# DfMUX_ADC.net
KiCad netlist of a schematic drawn in Altium Designer
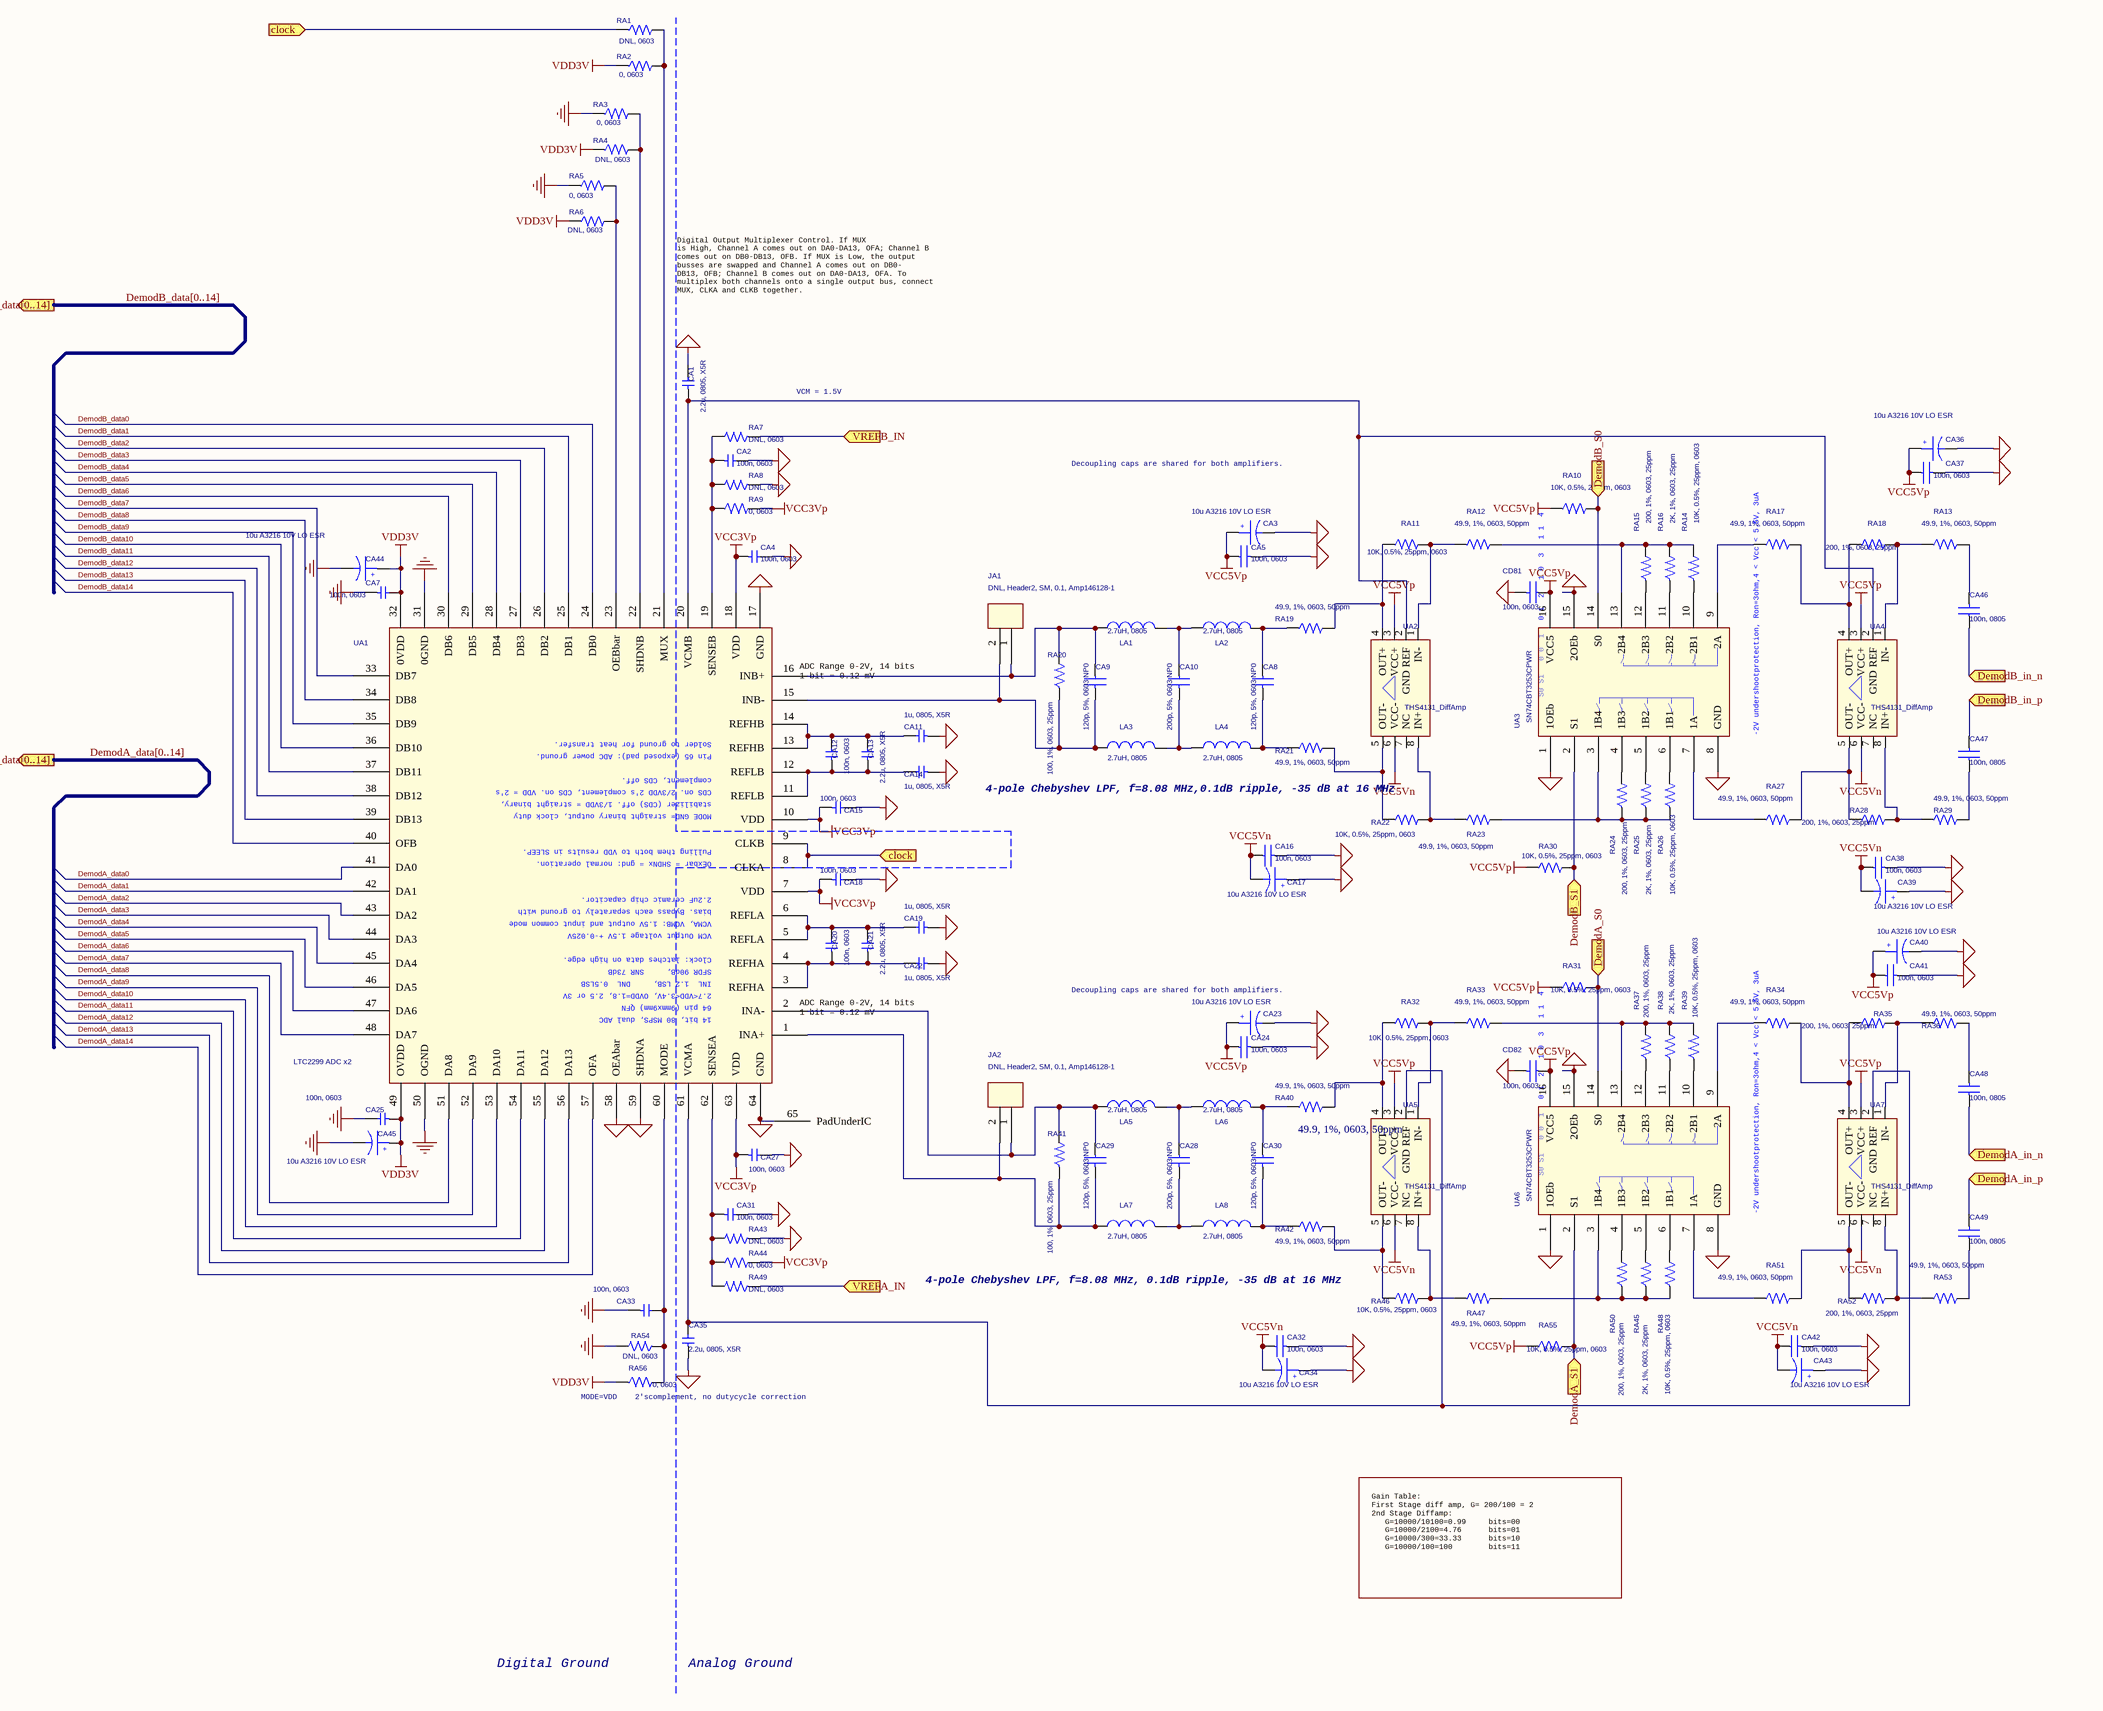
[diagram p0: DfMUX_ADC.SchDoc]

(export (version "E")
  (design (tool "Eeschema 10.0.6"))
  (components
    (comp (ref "CA1") (value "2.2u, 0805, X5R") (footprint "0805C") (libsource (lib "*") (part "C")))
    (comp (ref "CA2") (value "100n, 0603") (footprint "0603C") (libsource (lib "*") (part "C")))
    (comp (ref "CA3") (value "10u A3216 10V LO ESR") (libsource (lib "*") (part "CAPACITOR POL")))
    (comp (ref "CA4") (value "100n, 0603") (footprint "0603C") (libsource (lib "*") (part "C")))
    (comp (ref "CA5")
      (value "100n, 0603")
      (footprint "0603C")
      (libsource (lib "*") (part "CAPACITOR NON-POL"))
    )
    (comp (ref "CA7") (value "100n, 0603") (footprint "0603C") (libsource (lib "*") (part "C")))
    (comp (ref "CA8")
      (value "120p, 5%, 0603 NP0")
      (footprint "0603C")
      (libsource (lib "*") (part "CAPACITOR NON-POL"))
    )
    (comp (ref "CA9")
      (value "120p, 5%, 0603 NP0")
      (footprint "0603C")
      (libsource (lib "*") (part "CAPACITOR NON-POL"))
    )
    (comp (ref "CA10")
      (value "200p, 5%, 0603 NP0")
      (footprint "0603C")
      (libsource (lib "*") (part "CAPACITOR NON-POL"))
    )
    (comp (ref "CA11") (value "1u, 0805, X5R") (footprint "0805C") (libsource (lib "*") (part "C")))
    (comp (ref "CA12") (value "100n, 0603") (footprint "0603C") (libsource (lib "*") (part "C")))
    (comp (ref "CA13") (value "2.2u, 0805, X5R") (footprint "0805C") (libsource (lib "*") (part "C")))
    (comp (ref "CA14") (value "1u, 0805, X5R") (footprint "0805C") (libsource (lib "*") (part "C")))
    (comp (ref "CA15") (value "100n, 0603") (footprint "0603C") (libsource (lib "*") (part "C")))
    (comp (ref "CA16")
      (value "100n, 0603")
      (footprint "0603C")
      (libsource (lib "*") (part "CAPACITOR NON-POL"))
    )
    (comp (ref "CA17") (value "10u A3216 10V LO ESR") (libsource (lib "*") (part "CAPACITOR POL")))
    (comp (ref "CA18") (value "100n, 0603") (footprint "0603C") (libsource (lib "*") (part "C")))
    (comp (ref "CA19") (value "1u, 0805, X5R") (footprint "0805C") (libsource (lib "*") (part "C")))
    (comp (ref "CA20") (value "100n, 0603") (footprint "0603C") (libsource (lib "*") (part "C")))
    (comp (ref "CA21") (value "2.2u, 0805, X5R") (footprint "0805C") (libsource (lib "*") (part "C")))
    (comp (ref "CA22") (value "1u, 0805, X5R") (footprint "0805C") (libsource (lib "*") (part "C")))
    (comp (ref "CA23") (value "10u A3216 10V LO ESR") (libsource (lib "*") (part "CAPACITOR POL")))
    (comp (ref "CA24")
      (value "100n, 0603")
      (footprint "0603C")
      (libsource (lib "*") (part "CAPACITOR NON-POL"))
    )
    (comp (ref "CA25") (value "100n, 0603") (footprint "0603C") (libsource (lib "*") (part "C")))
    (comp (ref "CA27") (value "100n, 0603") (footprint "0603C") (libsource (lib "*") (part "C")))
    (comp (ref "CA28") (value "200p, 5%, 0603 NP0") (libsource (lib "*") (part "CAPACITOR NON-POL")))
    (comp (ref "CA29")
      (value "120p, 5%, 0603 NP0")
      (footprint "0603C")
      (libsource (lib "*") (part "CAPACITOR NON-POL"))
    )
    (comp (ref "CA30")
      (value "120p, 5%, 0603 NP0")
      (footprint "0603C")
      (libsource (lib "*") (part "CAPACITOR NON-POL"))
    )
    (comp (ref "CA31") (value "100n, 0603") (footprint "0603C") (libsource (lib "*") (part "C")))
    (comp (ref "CA32")
      (value "100n, 0603")
      (footprint "0603C")
      (libsource (lib "*") (part "CAPACITOR NON-POL"))
    )
    (comp (ref "CA33") (value "100n, 0603") (footprint "0603C") (libsource (lib "*") (part "C")))
    (comp (ref "CA34") (value "10u A3216 10V LO ESR") (libsource (lib "*") (part "CAPACITOR POL")))
    (comp (ref "CA35") (value "2.2u, 0805, X5R") (footprint "0805C") (libsource (lib "*") (part "C")))
    (comp (ref "CA36") (value "10u A3216 10V LO ESR") (libsource (lib "*") (part "CAPACITOR POL")))
    (comp (ref "CA37")
      (value "100n, 0603")
      (footprint "0603C")
      (libsource (lib "*") (part "CAPACITOR NON-POL"))
    )
    (comp (ref "CA38")
      (value "100n, 0603")
      (footprint "0603C")
      (libsource (lib "*") (part "CAPACITOR NON-POL"))
    )
    (comp (ref "CA39") (value "10u A3216 10V LO ESR") (libsource (lib "*") (part "CAPACITOR POL")))
    (comp (ref "CA40") (value "10u A3216 10V LO ESR") (libsource (lib "*") (part "CAPACITOR POL")))
    (comp (ref "CA41")
      (value "100n, 0603")
      (footprint "0603C")
      (libsource (lib "*") (part "CAPACITOR NON-POL"))
    )
    (comp (ref "CA42")
      (value "100n, 0603")
      (footprint "0603C")
      (libsource (lib "*") (part "CAPACITOR NON-POL"))
    )
    (comp (ref "CA43") (value "10u A3216 10V LO ESR") (libsource (lib "*") (part "CAPACITOR POL")))
    (comp (ref "CA44") (value "10u A3216 10V LO ESR") (libsource (lib "*") (part "CAPACITOR POL")))
    (comp (ref "CA45") (value "10u A3216 10V LO ESR") (libsource (lib "*") (part "CAPACITOR POL")))
    (comp (ref "CA46")
      (value "100n, 0805")
      (footprint "0805C")
      (libsource (lib "*") (part "CAPACITOR NON-POL"))
    )
    (comp (ref "CA47")
      (value "100n, 0805")
      (footprint "0805C")
      (libsource (lib "*") (part "CAPACITOR NON-POL"))
    )
    (comp (ref "CA48")
      (value "100n, 0805")
      (footprint "0805C")
      (libsource (lib "*") (part "CAPACITOR NON-POL"))
    )
    (comp (ref "CA49")
      (value "100n, 0805")
      (footprint "0805C")
      (libsource (lib "*") (part "CAPACITOR NON-POL"))
    )
    (comp (ref "CD81")
      (value "100n, 0603")
      (footprint "0603C")
      (libsource (lib "*") (part "CAPACITOR NON-POL"))
    )
    (comp (ref "CD82")
      (value "100n, 0603")
      (footprint "0603C")
      (libsource (lib "*") (part "CAPACITOR NON-POL"))
    )
    (comp (ref "JA1")
      (value "DNL, Header2, SM, 0.1, Amp146128-1")
      (libsource (lib "*") (part "CONN_TRBLK_2"))
    )
    (comp (ref "JA2")
      (value "DNL, Header2, SM, 0.1, Amp146128-1")
      (libsource (lib "*") (part "CONN_TRBLK_2"))
    )
    (comp (ref "LA1") (value "2.7uH, 0805") (libsource (lib "*") (part "INDUCTOR/SM")))
    (comp (ref "LA2") (value "2.7uH, 0805") (libsource (lib "*") (part "INDUCTOR/SM")))
    (comp (ref "LA3") (value "2.7uH, 0805") (libsource (lib "*") (part "INDUCTOR/SM")))
    (comp (ref "LA4") (value "2.7uH, 0805") (libsource (lib "*") (part "INDUCTOR/SM")))
    (comp (ref "LA5") (value "2.7uH, 0805") (libsource (lib "*") (part "INDUCTOR/SM")))
    (comp (ref "LA6") (value "2.7uH, 0805") (libsource (lib "*") (part "INDUCTOR/SM")))
    (comp (ref "LA7") (value "2.7uH, 0805") (libsource (lib "*") (part "INDUCTOR/SM")))
    (comp (ref "LA8") (value "2.7uH, 0805") (libsource (lib "*") (part "INDUCTOR/SM")))
    (comp (ref "RA1") (value "DNL, 0603") (footprint "0603R") (libsource (lib "*") (part "R_Dup2")))
    (comp (ref "RA2") (value "0, 0603") (footprint "0603R") (libsource (lib "*") (part "R_Dup2")))
    (comp (ref "RA3") (value "0, 0603") (footprint "0603R") (libsource (lib "*") (part "R_Dup2")))
    (comp (ref "RA4") (value "DNL, 0603") (footprint "0603R") (libsource (lib "*") (part "R_Dup2")))
    (comp (ref "RA5") (value "0, 0603") (footprint "0603R") (libsource (lib "*") (part "R_Dup2")))
    (comp (ref "RA6") (value "DNL, 0603") (footprint "0603R") (libsource (lib "*") (part "R_Dup2")))
    (comp (ref "RA7") (value "DNL, 0603") (footprint "0603R") (libsource (lib "*") (part "R_Dup2")))
    (comp (ref "RA8") (value "DNL, 0603") (footprint "0603R") (libsource (lib "*") (part "R_Dup2")))
    (comp (ref "RA9") (value "0, 0603") (footprint "0603R") (libsource (lib "*") (part "R_Dup2")))
    (comp (ref "RA10")
      (value "10K, 0.5%, 25ppm, 0603")
      (footprint "0603R")
      (libsource (lib "*") (part "R_Dup2"))
    )
    (comp (ref "RA11")
      (value "10K, 0.5%, 25ppm, 0603")
      (footprint "0603R")
      (libsource (lib "*") (part "R_Dup2"))
    )
    (comp (ref "RA12")
      (value "49.9, 1%, 0603, 50ppm")
      (footprint "0603R")
      (libsource (lib "*") (part "R_Dup2"))
    )
    (comp (ref "RA13")
      (value "49.9, 1%, 0603, 50ppm")
      (footprint "0603R")
      (libsource (lib "*") (part "R_Dup2"))
    )
    (comp (ref "RA14")
      (value "10K, 0.5%, 25ppm, 0603")
      (footprint "0603R")
      (libsource (lib "*") (part "R_Dup2"))
    )
    (comp (ref "RA15")
      (value "200, 1%, 0603, 25ppm")
      (footprint "0603R")
      (libsource (lib "*") (part "R_Dup2"))
    )
    (comp (ref "RA16")
      (value "2K, 1%, 0603, 25ppm")
      (footprint "0603R")
      (libsource (lib "*") (part "R_Dup2"))
    )
    (comp (ref "RA17")
      (value "49.9, 1%, 0603, 50ppm")
      (footprint "0603R")
      (libsource (lib "*") (part "R_Dup2"))
    )
    (comp (ref "RA18")
      (value "200, 1%, 0603, 25ppm")
      (footprint "0603R")
      (libsource (lib "*") (part "R_Dup2"))
    )
    (comp (ref "RA19")
      (value "49.9, 1%, 0603, 50ppm")
      (footprint "0603R")
      (libsource (lib "*") (part "R_Dup2"))
    )
    (comp (ref "RA20")
      (value "100, 1%, 0603, 25ppm")
      (footprint "0603R")
      (libsource (lib "*") (part "R_Dup2"))
    )
    (comp (ref "RA21")
      (value "49.9, 1%, 0603, 50ppm")
      (footprint "0603R")
      (libsource (lib "*") (part "R_Dup2"))
    )
    (comp (ref "RA22")
      (value "10K, 0.5%, 25ppm, 0603")
      (footprint "0603R")
      (libsource (lib "*") (part "R_Dup2"))
    )
    (comp (ref "RA23")
      (value "49.9, 1%, 0603, 50ppm")
      (footprint "0603R")
      (libsource (lib "*") (part "R_Dup2"))
    )
    (comp (ref "RA24")
      (value "200, 1%, 0603, 25ppm")
      (footprint "0603R")
      (libsource (lib "*") (part "R_Dup2"))
    )
    (comp (ref "RA25")
      (value "2K, 1%, 0603, 25ppm")
      (footprint "0603R")
      (libsource (lib "*") (part "R_Dup2"))
    )
    (comp (ref "RA26")
      (value "10K, 0.5%, 25ppm, 0603")
      (footprint "0603R")
      (libsource (lib "*") (part "R_Dup2"))
    )
    (comp (ref "RA27")
      (value "49.9, 1%, 0603, 50ppm")
      (footprint "0603R")
      (libsource (lib "*") (part "R_Dup2"))
    )
    (comp (ref "RA28")
      (value "200, 1%, 0603, 25ppm")
      (footprint "0603R")
      (libsource (lib "*") (part "R_Dup2"))
    )
    (comp (ref "RA29")
      (value "49.9, 1%, 0603, 50ppm")
      (footprint "0603R")
      (libsource (lib "*") (part "R_Dup2"))
    )
    (comp (ref "RA30")
      (value "10K, 0.5%, 25ppm, 0603")
      (footprint "0603R")
      (libsource (lib "*") (part "R_Dup2"))
    )
    (comp (ref "RA31")
      (value "10K, 0.5%, 25ppm, 0603")
      (footprint "0603R")
      (libsource (lib "*") (part "R_Dup2"))
    )
    (comp (ref "RA32")
      (value "10K, 0.5%, 25ppm, 0603")
      (footprint "0603R")
      (libsource (lib "*") (part "R_Dup2"))
    )
    (comp (ref "RA33")
      (value "49.9, 1%, 0603, 50ppm")
      (footprint "0603R")
      (libsource (lib "*") (part "R_Dup2"))
    )
    (comp (ref "RA34")
      (value "49.9, 1%, 0603, 50ppm")
      (footprint "0603R")
      (libsource (lib "*") (part "R_Dup2"))
    )
    (comp (ref "RA35")
      (value "200, 1%, 0603, 25ppm")
      (footprint "0603R")
      (libsource (lib "*") (part "R_Dup2"))
    )
    (comp (ref "RA36")
      (value "49.9, 1%, 0603, 50ppm")
      (footprint "0603R")
      (libsource (lib "*") (part "R_Dup2"))
    )
    (comp (ref "RA37")
      (value "200, 1%, 0603, 25ppm")
      (footprint "0603R")
      (libsource (lib "*") (part "R_Dup2"))
    )
    (comp (ref "RA38")
      (value "2K, 1%, 0603, 25ppm")
      (footprint "0603R")
      (libsource (lib "*") (part "R_Dup2"))
    )
    (comp (ref "RA39")
      (value "10K, 0.5%, 25ppm, 0603")
      (footprint "0603R")
      (libsource (lib "*") (part "R_Dup2"))
    )
    (comp (ref "RA40")
      (value "49.9, 1%, 0603, 50ppm")
      (footprint "0603R")
      (fields (field (name "ALTIUM_VALUE") "49.9, 1%, 0603, 50ppm"))
      (libsource (lib "*") (part "R_Dup2"))
    )
    (comp (ref "RA41")
      (value "100, 1%, 0603, 25ppm")
      (footprint "0603R")
      (libsource (lib "*") (part "R_Dup2"))
    )
    (comp (ref "RA42")
      (value "49.9, 1%, 0603, 50ppm")
      (footprint "0603R")
      (libsource (lib "*") (part "R_Dup2"))
    )
    (comp (ref "RA43") (value "DNL, 0603") (footprint "0603R") (libsource (lib "*") (part "R_Dup2")))
    (comp (ref "RA44") (value "0, 0603") (footprint "0603R") (libsource (lib "*") (part "R_Dup2")))
    (comp (ref "RA45")
      (value "2K, 1%, 0603, 25ppm")
      (footprint "0603R")
      (libsource (lib "*") (part "R_Dup2"))
    )
    (comp (ref "RA46")
      (value "10K, 0.5%, 25ppm, 0603")
      (footprint "0603R")
      (libsource (lib "*") (part "R_Dup2"))
    )
    (comp (ref "RA47")
      (value "49.9, 1%, 0603, 50ppm")
      (footprint "0603R")
      (libsource (lib "*") (part "R_Dup2"))
    )
    (comp (ref "RA48")
      (value "10K, 0.5%, 25ppm, 0603")
      (footprint "0603R")
      (libsource (lib "*") (part "R_Dup2"))
    )
    (comp (ref "RA49") (value "DNL, 0603") (footprint "0603R") (libsource (lib "*") (part "R_Dup2")))
    (comp (ref "RA50")
      (value "200, 1%, 0603, 25ppm")
      (footprint "0603R")
      (libsource (lib "*") (part "R_Dup2"))
    )
    (comp (ref "RA51")
      (value "49.9, 1%, 0603, 50ppm")
      (footprint "0603R")
      (libsource (lib "*") (part "R_Dup2"))
    )
    (comp (ref "RA52")
      (value "200, 1%, 0603, 25ppm")
      (footprint "0603R")
      (libsource (lib "*") (part "R_Dup2"))
    )
    (comp (ref "RA53")
      (value "49.9, 1%, 0603, 50ppm")
      (footprint "0603R")
      (libsource (lib "*") (part "R_Dup2"))
    )
    (comp (ref "RA54") (value "DNL, 0603") (footprint "0603R") (libsource (lib "*") (part "R_Dup2")))
    (comp (ref "RA55")
      (value "10K, 0.5%, 25ppm, 0603")
      (footprint "0603R")
      (libsource (lib "*") (part "R_Dup2"))
    )
    (comp (ref "RA56") (value "0, 0603") (footprint "0603R") (libsource (lib "*") (part "R_Dup2")))
    (comp (ref "UA1")
      (value "LTC2299 ADC x2")
      (footprint "QFN64(9X9)")
      (libsource (lib "*") (part "LTC2299 ADC x2_3"))
    )
    (comp (ref "UA2") (value "THS4131_DiffAmp") (libsource (lib "*") (part "THS4131_DiffAmp_0")))
    (comp (ref "UA3")
      (value "SN74CBT3253CPWR")
      (footprint "TSSOP16")
      (libsource (lib "*") (part "SN74CBT3253C 4MUX"))
    )
    (comp (ref "UA4") (value "THS4131_DiffAmp") (libsource (lib "*") (part "THS4131_DiffAmp_0")))
    (comp (ref "UA5") (value "THS4131_DiffAmp") (libsource (lib "*") (part "THS4131_DiffAmp_0")))
    (comp (ref "UA6")
      (value "SN74CBT3253CPWR")
      (footprint "TSSOP16")
      (libsource (lib "*") (part "SN74CBT3253C 4MUX"))
    )
    (comp (ref "UA7") (value "THS4131_DiffAmp") (libsource (lib "*") (part "THS4131_DiffAmp_0")))
  )
  (nets
    (net (code "1") (name "/DemodA_S0") (class "Default")
      (node (ref "RA31") (pin "2") (pinfunction "2_2") (pintype "passive"))
      (node (ref "UA6") (pin "14") (pinfunction "S0_14") (pintype "passive"))
    )
    (net (code "2") (name "/DemodA_S1") (class "Default")
      (node (ref "RA55") (pin "2") (pinfunction "2_2") (pintype "passive"))
      (node (ref "UA6") (pin "2") (pinfunction "S1_2") (pintype "passive"))
    )
    (net (code "3") (name "/DemodA_data0") (class "Default")
      (node (ref "UA1") (pin "41") (pinfunction "DA0_41") (pintype "passive"))
    )
    (net (code "4") (name "/DemodA_data1") (class "Default")
      (node (ref "UA1") (pin "42") (pinfunction "DA1_42") (pintype "passive"))
    )
    (net (code "5") (name "/DemodA_data2") (class "Default")
      (node (ref "UA1") (pin "43") (pinfunction "DA2_43") (pintype "passive"))
    )
    (net (code "6") (name "/DemodA_data3") (class "Default")
      (node (ref "UA1") (pin "44") (pinfunction "DA3_44") (pintype "passive"))
    )
    (net (code "7") (name "/DemodA_data4") (class "Default")
      (node (ref "UA1") (pin "45") (pinfunction "DA4_45") (pintype "passive"))
    )
    (net (code "8") (name "/DemodA_data5") (class "Default")
      (node (ref "UA1") (pin "46") (pinfunction "DA5_46") (pintype "passive"))
    )
    (net (code "9") (name "/DemodA_data6") (class "Default")
      (node (ref "UA1") (pin "47") (pinfunction "DA6_47") (pintype "passive"))
    )
    (net (code "10") (name "/DemodA_data7") (class "Default")
      (node (ref "UA1") (pin "48") (pinfunction "DA7_48") (pintype "passive"))
    )
    (net (code "11") (name "/DemodA_data8") (class "Default")
      (node (ref "UA1") (pin "51") (pinfunction "DA8_51") (pintype "passive"))
    )
    (net (code "12") (name "/DemodA_data9") (class "Default")
      (node (ref "UA1") (pin "52") (pinfunction "DA9_52") (pintype "passive"))
    )
    (net (code "13") (name "/DemodA_data10") (class "Default")
      (node (ref "UA1") (pin "53") (pinfunction "DA10_53") (pintype "passive"))
    )
    (net (code "14") (name "/DemodA_data11") (class "Default")
      (node (ref "UA1") (pin "54") (pinfunction "DA11_54") (pintype "passive"))
    )
    (net (code "15") (name "/DemodA_data12") (class "Default")
      (node (ref "UA1") (pin "55") (pinfunction "DA12_55") (pintype "passive"))
    )
    (net (code "16") (name "/DemodA_data13") (class "Default")
      (node (ref "UA1") (pin "56") (pinfunction "DA13_56") (pintype "passive"))
    )
    (net (code "17") (name "/DemodA_data14") (class "Default")
      (node (ref "UA1") (pin "57") (pinfunction "OFA_57") (pintype "passive"))
    )
    (net (code "19") (name "/DemodA_in_n") (class "Default")
      (node (ref "CA48") (pin "1") (pinfunction "1_1") (pintype "passive"))
    )
    (net (code "20") (name "/DemodA_in_p") (class "Default")
      (node (ref "CA49") (pin "2") (pinfunction "2_2") (pintype "passive"))
    )
    (net (code "21") (name "/DemodB_S0") (class "Default")
      (node (ref "RA10") (pin "2") (pinfunction "2_2") (pintype "passive"))
      (node (ref "UA3") (pin "14") (pinfunction "S0_14") (pintype "passive"))
    )
    (net (code "22") (name "/DemodB_S1") (class "Default")
      (node (ref "RA30") (pin "2") (pinfunction "2_2") (pintype "passive"))
      (node (ref "UA3") (pin "2") (pinfunction "S1_2") (pintype "passive"))
    )
    (net (code "23") (name "/DemodB_data0") (class "Default")
      (node (ref "UA1") (pin "24") (pinfunction "DB0_24") (pintype "passive"))
    )
    (net (code "24") (name "/DemodB_data1") (class "Default")
      (node (ref "UA1") (pin "25") (pinfunction "DB1_25") (pintype "passive"))
    )
    (net (code "25") (name "/DemodB_data2") (class "Default")
      (node (ref "UA1") (pin "26") (pinfunction "DB2_26") (pintype "passive"))
    )
    (net (code "26") (name "/DemodB_data3") (class "Default")
      (node (ref "UA1") (pin "27") (pinfunction "DB3_27") (pintype "passive"))
    )
    (net (code "27") (name "/DemodB_data4") (class "Default")
      (node (ref "UA1") (pin "28") (pinfunction "DB4_28") (pintype "passive"))
    )
    (net (code "28") (name "/DemodB_data5") (class "Default")
      (node (ref "UA1") (pin "29") (pinfunction "DB5_29") (pintype "passive"))
    )
    (net (code "29") (name "/DemodB_data6") (class "Default")
      (node (ref "UA1") (pin "30") (pinfunction "DB6_30") (pintype "passive"))
    )
    (net (code "30") (name "/DemodB_data7") (class "Default")
      (node (ref "UA1") (pin "33") (pinfunction "DB7_33") (pintype "passive"))
    )
    (net (code "31") (name "/DemodB_data8") (class "Default")
      (node (ref "UA1") (pin "34") (pinfunction "DB8_34") (pintype "passive"))
    )
    (net (code "32") (name "/DemodB_data9") (class "Default")
      (node (ref "UA1") (pin "35") (pinfunction "DB9_35") (pintype "passive"))
    )
    (net (code "33") (name "/DemodB_data10") (class "Default")
      (node (ref "UA1") (pin "36") (pinfunction "DB10_36") (pintype "passive"))
    )
    (net (code "34") (name "/DemodB_data11") (class "Default")
      (node (ref "UA1") (pin "37") (pinfunction "DB11_37") (pintype "passive"))
    )
    (net (code "35") (name "/DemodB_data12") (class "Default")
      (node (ref "UA1") (pin "38") (pinfunction "DB12_38") (pintype "passive"))
    )
    (net (code "36") (name "/DemodB_data13") (class "Default")
      (node (ref "UA1") (pin "39") (pinfunction "DB13_39") (pintype "passive"))
    )
    (net (code "37") (name "/DemodB_data14") (class "Default")
      (node (ref "UA1") (pin "40") (pinfunction "OFB_40") (pintype "passive"))
    )
    (net (code "39") (name "/DemodB_in_n") (class "Default")
      (node (ref "CA46") (pin "1") (pinfunction "1_1") (pintype "passive"))
    )
    (net (code "40") (name "/DemodB_in_p") (class "Default")
      (node (ref "CA47") (pin "2") (pinfunction "2_2") (pintype "passive"))
    )
    (net (code "41") (name "/VREFA_IN") (class "Default")
      (node (ref "RA49") (pin "1") (pinfunction "1_1") (pintype "passive"))
    )
    (net (code "42") (name "/VREFB_IN") (class "Default")
      (node (ref "RA7") (pin "1") (pinfunction "1_1") (pintype "passive"))
    )
    (net (code "43") (name "/clock") (class "Default")
      (node (ref "RA1") (pin "1") (pinfunction "1_1") (pintype "passive"))
      (node (ref "UA1") (pin "8") (pinfunction "CLKA_8") (pintype "passive"))
      (node (ref "UA1") (pin "9") (pinfunction "CLKB_9") (pintype "passive"))
    )
    (net (code "44") (name "GND_DIG") (class "Default")
      (node (ref "CA25") (pin "2") (pinfunction "2_2") (pintype "passive"))
      (node (ref "CA33") (pin "1") (pinfunction "1_1") (pintype "passive"))
      (node (ref "CA44") (pin "2") (pinfunction "2_2") (pintype "passive"))
      (node (ref "CA45") (pin "2") (pinfunction "2_2") (pintype "passive"))
      (node (ref "CA7") (pin "1") (pinfunction "1_1") (pintype "passive"))
      (node (ref "RA3") (pin "1") (pinfunction "1_1") (pintype "passive"))
      (node (ref "RA5") (pin "1") (pinfunction "1_1") (pintype "passive"))
      (node (ref "RA54") (pin "2") (pinfunction "2_2") (pintype "passive"))
      (node (ref "UA1") (pin "31") (pinfunction "0GND_31") (pintype "passive"))
      (node (ref "UA1") (pin "50") (pinfunction "OGND_50") (pintype "passive"))
    )
    (net (code "45") (name "GND_SIGNAL") (class "Default")
      (node (ref "CA1") (pin "2") (pinfunction "2_2") (pintype "passive"))
      (node (ref "CA11") (pin "1") (pinfunction "1_1") (pintype "passive"))
      (node (ref "CA14") (pin "1") (pinfunction "1_1") (pintype "passive"))
      (node (ref "CA15") (pin "2") (pinfunction "2_2") (pintype "passive"))
      (node (ref "CA16") (pin "2") (pinfunction "2_2") (pintype "passive"))
      (node (ref "CA17") (pin "1") (pinfunction "1_1") (pintype "passive"))
      (node (ref "CA18") (pin "2") (pinfunction "2_2") (pintype "passive"))
      (node (ref "CA19") (pin "1") (pinfunction "1_1") (pintype "passive"))
      (node (ref "CA2") (pin "2") (pinfunction "2_2") (pintype "passive"))
      (node (ref "CA22") (pin "1") (pinfunction "1_1") (pintype "passive"))
      (node (ref "CA23") (pin "2") (pinfunction "2_2") (pintype "passive"))
      (node (ref "CA24") (pin "2") (pinfunction "2_2") (pintype "passive"))
      (node (ref "CA27") (pin "2") (pinfunction "2_2") (pintype "passive"))
      (node (ref "CA3") (pin "2") (pinfunction "2_2") (pintype "passive"))
      (node (ref "CA31") (pin "2") (pinfunction "2_2") (pintype "passive"))
      (node (ref "CA32") (pin "2") (pinfunction "2_2") (pintype "passive"))
      (node (ref "CA34") (pin "1") (pinfunction "1_1") (pintype "passive"))
      (node (ref "CA35") (pin "1") (pinfunction "1_1") (pintype "passive"))
      (node (ref "CA36") (pin "2") (pinfunction "2_2") (pintype "passive"))
      (node (ref "CA37") (pin "2") (pinfunction "2_2") (pintype "passive"))
      (node (ref "CA38") (pin "2") (pinfunction "2_2") (pintype "passive"))
      (node (ref "CA39") (pin "1") (pinfunction "1_1") (pintype "passive"))
      (node (ref "CA4") (pin "2") (pinfunction "2_2") (pintype "passive"))
      (node (ref "CA40") (pin "2") (pinfunction "2_2") (pintype "passive"))
      (node (ref "CA41") (pin "2") (pinfunction "2_2") (pintype "passive"))
      (node (ref "CA42") (pin "2") (pinfunction "2_2") (pintype "passive"))
      (node (ref "CA43") (pin "1") (pinfunction "1_1") (pintype "passive"))
      (node (ref "CA5") (pin "2") (pinfunction "2_2") (pintype "passive"))
      (node (ref "CD81") (pin "2") (pinfunction "2_2") (pintype "passive"))
      (node (ref "CD82") (pin "2") (pinfunction "2_2") (pintype "passive"))
      (node (ref "RA43") (pin "1") (pinfunction "1_1") (pintype "passive"))
      (node (ref "RA8") (pin "1") (pinfunction "1_1") (pintype "passive"))
      (node (ref "UA1") (pin "17") (pinfunction "GND_17") (pintype "passive"))
      (node (ref "UA1") (pin "58") (pinfunction "OEAbar_58") (pintype "passive"))
      (node (ref "UA1") (pin "59") (pinfunction "SHDNA_59") (pintype "passive"))
      (node (ref "UA1") (pin "64") (pinfunction "GND_64") (pintype "passive"))
      (node (ref "UA1") (pin "65") (pinfunction "PadUnderIC_65") (pintype "passive"))
      (node (ref "UA3") (pin "1") (pinfunction "1OEb_1") (pintype "passive"))
      (node (ref "UA3") (pin "15") (pinfunction "2OEb_15") (pintype "passive"))
      (node (ref "UA3") (pin "8") (pinfunction "GND_8") (pintype "passive"))
      (node (ref "UA6") (pin "1") (pinfunction "1OEb_1") (pintype "passive"))
      (node (ref "UA6") (pin "15") (pinfunction "2OEb_15") (pintype "passive"))
      (node (ref "UA6") (pin "8") (pinfunction "GND_8") (pintype "passive"))
    )
    (net (code "46") (name "Net-(CA8-Pad1)") (class "Default")
      (node (ref "CA8") (pin "1") (pinfunction "1_1") (pintype "passive"))
      (node (ref "LA2") (pin "2") (pinfunction "2_2") (pintype "passive"))
      (node (ref "RA19") (pin "1") (pinfunction "1_1") (pintype "passive"))
    )
    (net (code "47") (name "Net-(CA8-Pad2)") (class "Default")
      (node (ref "CA8") (pin "2") (pinfunction "2_2") (pintype "passive"))
      (node (ref "LA4") (pin "2") (pinfunction "2_2") (pintype "passive"))
      (node (ref "RA21") (pin "1") (pinfunction "1_1") (pintype "passive"))
    )
    (net (code "48") (name "Net-(CA10-Pad1)") (class "Default")
      (node (ref "CA10") (pin "1") (pinfunction "1_1") (pintype "passive"))
      (node (ref "LA1") (pin "2") (pinfunction "2_2") (pintype "passive"))
      (node (ref "LA2") (pin "1") (pinfunction "1_1") (pintype "passive"))
    )
    (net (code "49") (name "Net-(CA10-Pad2)") (class "Default")
      (node (ref "CA10") (pin "2") (pinfunction "2_2") (pintype "passive"))
      (node (ref "LA3") (pin "2") (pinfunction "2_2") (pintype "passive"))
      (node (ref "LA4") (pin "1") (pinfunction "1_1") (pintype "passive"))
    )
    (net (code "50") (name "Net-(CA11-Pad2)") (class "Default")
      (node (ref "CA11") (pin "2") (pinfunction "2_2") (pintype "passive"))
      (node (ref "CA12") (pin "2") (pinfunction "2_2") (pintype "passive"))
      (node (ref "CA13") (pin "2") (pinfunction "2_2") (pintype "passive"))
      (node (ref "UA1") (pin "13") (pinfunction "REFHB_13") (pintype "passive"))
      (node (ref "UA1") (pin "14") (pinfunction "REFHB_14") (pintype "passive"))
    )
    (net (code "51") (name "Net-(CA12-Pad1)") (class "Default")
      (node (ref "CA12") (pin "1") (pinfunction "1_1") (pintype "passive"))
      (node (ref "CA13") (pin "1") (pinfunction "1_1") (pintype "passive"))
      (node (ref "CA14") (pin "2") (pinfunction "2_2") (pintype "passive"))
      (node (ref "UA1") (pin "11") (pinfunction "REFLB_11") (pintype "passive"))
      (node (ref "UA1") (pin "12") (pinfunction "REFLB_12") (pintype "passive"))
    )
    (net (code "52") (name "Net-(CA19-Pad2)") (class "Default")
      (node (ref "CA19") (pin "2") (pinfunction "2_2") (pintype "passive"))
      (node (ref "CA20") (pin "2") (pinfunction "2_2") (pintype "passive"))
      (node (ref "CA21") (pin "2") (pinfunction "2_2") (pintype "passive"))
      (node (ref "UA1") (pin "5") (pinfunction "REFLA_5") (pintype "passive"))
      (node (ref "UA1") (pin "6") (pinfunction "REFLA_6") (pintype "passive"))
    )
    (net (code "53") (name "Net-(CA20-Pad1)") (class "Default")
      (node (ref "CA20") (pin "1") (pinfunction "1_1") (pintype "passive"))
      (node (ref "CA21") (pin "1") (pinfunction "1_1") (pintype "passive"))
      (node (ref "CA22") (pin "2") (pinfunction "2_2") (pintype "passive"))
      (node (ref "UA1") (pin "3") (pinfunction "REFHA_3") (pintype "passive"))
      (node (ref "UA1") (pin "4") (pinfunction "REFHA_4") (pintype "passive"))
    )
    (net (code "54") (name "Net-(CA28-Pad1)") (class "Default")
      (node (ref "CA28") (pin "1") (pinfunction "1_1") (pintype "passive"))
      (node (ref "LA5") (pin "2") (pinfunction "2_2") (pintype "passive"))
      (node (ref "LA6") (pin "1") (pinfunction "1_1") (pintype "passive"))
    )
    (net (code "55") (name "Net-(CA28-Pad2)") (class "Default")
      (node (ref "CA28") (pin "2") (pinfunction "2_2") (pintype "passive"))
      (node (ref "LA7") (pin "2") (pinfunction "2_2") (pintype "passive"))
      (node (ref "LA8") (pin "1") (pinfunction "1_1") (pintype "passive"))
    )
    (net (code "56") (name "Net-(CA30-Pad1)") (class "Default")
      (node (ref "CA30") (pin "1") (pinfunction "1_1") (pintype "passive"))
      (node (ref "LA6") (pin "2") (pinfunction "2_2") (pintype "passive"))
      (node (ref "RA40") (pin "1") (pinfunction "1_1") (pintype "passive"))
    )
    (net (code "57") (name "Net-(CA30-Pad2)") (class "Default")
      (node (ref "CA30") (pin "2") (pinfunction "2_2") (pintype "passive"))
      (node (ref "LA8") (pin "2") (pinfunction "2_2") (pintype "passive"))
      (node (ref "RA42") (pin "1") (pinfunction "1_1") (pintype "passive"))
    )
    (net (code "58") (name "Net-(CA46-Pad2)") (class "Default")
      (node (ref "CA46") (pin "2") (pinfunction "2_2") (pintype "passive"))
      (node (ref "RA13") (pin "2") (pinfunction "2_2") (pintype "passive"))
    )
    (net (code "59") (name "Net-(CA47-Pad1)") (class "Default")
      (node (ref "CA47") (pin "1") (pinfunction "1_1") (pintype "passive"))
      (node (ref "RA29") (pin "2") (pinfunction "2_2") (pintype "passive"))
    )
    (net (code "60") (name "Net-(CA48-Pad2)") (class "Default")
      (node (ref "CA48") (pin "2") (pinfunction "2_2") (pintype "passive"))
      (node (ref "RA36") (pin "2") (pinfunction "2_2") (pintype "passive"))
    )
    (net (code "61") (name "Net-(CA49-Pad1)") (class "Default")
      (node (ref "CA49") (pin "1") (pinfunction "1_1") (pintype "passive"))
      (node (ref "RA53") (pin "2") (pinfunction "2_2") (pintype "passive"))
    )
    (net (code "62") (name "Net-(UA1-INA+)") (class "Default")
      (node (ref "CA29") (pin "2") (pinfunction "2_2") (pintype "passive"))
      (node (ref "JA2") (pin "2") (pinfunction "2_2") (pintype "passive"))
      (node (ref "LA7") (pin "1") (pinfunction "1_1") (pintype "passive"))
      (node (ref "RA41") (pin "1") (pinfunction "1_1") (pintype "passive"))
      (node (ref "UA1") (pin "1") (pinfunction "INA+_1") (pintype "passive"))
    )
    (net (code "63") (name "Net-(UA1-INA-)") (class "Default")
      (node (ref "CA29") (pin "1") (pinfunction "1_1") (pintype "passive"))
      (node (ref "JA2") (pin "1") (pinfunction "1_1") (pintype "passive"))
      (node (ref "LA5") (pin "1") (pinfunction "1_1") (pintype "passive"))
      (node (ref "RA41") (pin "2") (pinfunction "2_2") (pintype "passive"))
      (node (ref "UA1") (pin "2") (pinfunction "INA-_2") (pintype "passive"))
    )
    (net (code "64") (name "Net-(UA1-INB+)") (class "Default")
      (node (ref "CA9") (pin "1") (pinfunction "1_1") (pintype "passive"))
      (node (ref "JA1") (pin "1") (pinfunction "1_1") (pintype "passive"))
      (node (ref "LA1") (pin "1") (pinfunction "1_1") (pintype "passive"))
      (node (ref "RA20") (pin "2") (pinfunction "2_2") (pintype "passive"))
      (node (ref "UA1") (pin "16") (pinfunction "INB+_16") (pintype "passive"))
    )
    (net (code "65") (name "Net-(UA1-INB-)") (class "Default")
      (node (ref "CA9") (pin "2") (pinfunction "2_2") (pintype "passive"))
      (node (ref "JA1") (pin "2") (pinfunction "2_2") (pintype "passive"))
      (node (ref "LA3") (pin "1") (pinfunction "1_1") (pintype "passive"))
      (node (ref "RA20") (pin "1") (pinfunction "1_1") (pintype "passive"))
      (node (ref "UA1") (pin "15") (pinfunction "INB-_15") (pintype "passive"))
    )
    (net (code "66") (name "Net-(UA1-MODE)") (class "Default")
      (node (ref "CA33") (pin "2") (pinfunction "2_2") (pintype "passive"))
      (node (ref "RA54") (pin "1") (pinfunction "1_1") (pintype "passive"))
      (node (ref "RA56") (pin "2") (pinfunction "2_2") (pintype "passive"))
      (node (ref "UA1") (pin "60") (pinfunction "MODE_60") (pintype "passive"))
    )
    (net (code "67") (name "Net-(UA1-MUX)") (class "Default")
      (node (ref "RA1") (pin "2") (pinfunction "2_2") (pintype "passive"))
      (node (ref "RA2") (pin "2") (pinfunction "2_2") (pintype "passive"))
      (node (ref "UA1") (pin "21") (pinfunction "MUX_21") (pintype "passive"))
    )
    (net (code "68") (name "Net-(UA1-OEBbar)") (class "Default")
      (node (ref "RA5") (pin "2") (pinfunction "2_2") (pintype "passive"))
      (node (ref "RA6") (pin "2") (pinfunction "2_2") (pintype "passive"))
      (node (ref "UA1") (pin "23") (pinfunction "OEBbar_23") (pintype "passive"))
    )
    (net (code "69") (name "Net-(UA1-SENSEA)") (class "Default")
      (node (ref "CA31") (pin "1") (pinfunction "1_1") (pintype "passive"))
      (node (ref "RA43") (pin "2") (pinfunction "2_2") (pintype "passive"))
      (node (ref "RA44") (pin "1") (pinfunction "1_1") (pintype "passive"))
      (node (ref "RA49") (pin "2") (pinfunction "2_2") (pintype "passive"))
      (node (ref "UA1") (pin "62") (pinfunction "SENSEA_62") (pintype "passive"))
    )
    (net (code "70") (name "Net-(UA1-SENSEB)") (class "Default")
      (node (ref "CA2") (pin "1") (pinfunction "1_1") (pintype "passive"))
      (node (ref "RA7") (pin "2") (pinfunction "2_2") (pintype "passive"))
      (node (ref "RA8") (pin "2") (pinfunction "2_2") (pintype "passive"))
      (node (ref "RA9") (pin "1") (pinfunction "1_1") (pintype "passive"))
      (node (ref "UA1") (pin "19") (pinfunction "SENSEB_19") (pintype "passive"))
    )
    (net (code "71") (name "Net-(UA1-SHDNB)") (class "Default")
      (node (ref "RA3") (pin "2") (pinfunction "2_2") (pintype "passive"))
      (node (ref "RA4") (pin "2") (pinfunction "2_2") (pintype "passive"))
      (node (ref "UA1") (pin "22") (pinfunction "SHDNB_22") (pintype "passive"))
    )
    (net (code "72") (name "Net-(UA1-VCMA)") (class "Default")
      (node (ref "CA35") (pin "2") (pinfunction "2_2") (pintype "passive"))
      (node (ref "UA1") (pin "61") (pinfunction "VCMA_61") (pintype "passive"))
      (node (ref "UA5") (pin "2") (pinfunction "GND_REF_2") (pintype "passive"))
      (node (ref "UA7") (pin "2") (pinfunction "GND_REF_2") (pintype "passive"))
    )
    (net (code "73") (name "Net-(UA1-VCMB)") (class "Default")
      (node (ref "CA1") (pin "1") (pinfunction "1_1") (pintype "passive"))
      (node (ref "UA1") (pin "20") (pinfunction "VCMB_20") (pintype "passive"))
      (node (ref "UA2") (pin "2") (pinfunction "GND_REF_2") (pintype "passive"))
      (node (ref "UA4") (pin "2") (pinfunction "GND_REF_2") (pintype "passive"))
    )
    (net (code "74") (name "Net-(UA2-IN+)") (class "Default")
      (node (ref "RA22") (pin "2") (pinfunction "2_2") (pintype "passive"))
      (node (ref "RA23") (pin "1") (pinfunction "1_1") (pintype "passive"))
      (node (ref "UA2") (pin "8") (pinfunction "IN+_8") (pintype "passive"))
    )
    (net (code "75") (name "Net-(UA2-IN-)") (class "Default")
      (node (ref "RA11") (pin "2") (pinfunction "2_2") (pintype "passive"))
      (node (ref "RA12") (pin "1") (pinfunction "1_1") (pintype "passive"))
      (node (ref "UA2") (pin "1") (pinfunction "IN-_1") (pintype "passive"))
    )
    (net (code "76") (name "Net-(UA2-OUT+)") (class "Default")
      (node (ref "RA11") (pin "1") (pinfunction "1_1") (pintype "passive"))
      (node (ref "RA19") (pin "2") (pinfunction "2_2") (pintype "passive"))
      (node (ref "UA2") (pin "4") (pinfunction "OUT+_4") (pintype "passive"))
    )
    (net (code "77") (name "Net-(UA2-OUT-)") (class "Default")
      (node (ref "RA21") (pin "2") (pinfunction "2_2") (pintype "passive"))
      (node (ref "RA22") (pin "1") (pinfunction "1_1") (pintype "passive"))
      (node (ref "UA2") (pin "5") (pinfunction "OUT-_5") (pintype "passive"))
    )
    (net (code "78") (name "Net-(UA3-1A)") (class "Default")
      (node (ref "RA27") (pin "1") (pinfunction "1_1") (pintype "passive"))
      (node (ref "UA3") (pin "7") (pinfunction "1A_7") (pintype "passive"))
    )
    (net (code "79") (name "Net-(UA3-1B1)") (class "Default")
      (node (ref "RA26") (pin "2") (pinfunction "2_2") (pintype "passive"))
      (node (ref "UA3") (pin "6") (pinfunction "1B1_6") (pintype "passive"))
    )
    (net (code "80") (name "Net-(UA3-1B2)") (class "Default")
      (node (ref "RA25") (pin "2") (pinfunction "2_2") (pintype "passive"))
      (node (ref "UA3") (pin "5") (pinfunction "1B2_5") (pintype "passive"))
    )
    (net (code "81") (name "Net-(UA3-1B3)") (class "Default")
      (node (ref "RA24") (pin "2") (pinfunction "2_2") (pintype "passive"))
      (node (ref "UA3") (pin "4") (pinfunction "1B3_4") (pintype "passive"))
    )
    (net (code "82") (name "Net-(UA3-1B4)") (class "Default")
      (node (ref "RA23") (pin "2") (pinfunction "2_2") (pintype "passive"))
      (node (ref "RA24") (pin "1") (pinfunction "1_1") (pintype "passive"))
      (node (ref "RA25") (pin "1") (pinfunction "1_1") (pintype "passive"))
      (node (ref "RA26") (pin "1") (pinfunction "1_1") (pintype "passive"))
      (node (ref "UA3") (pin "3") (pinfunction "1B4_3") (pintype "passive"))
    )
    (net (code "83") (name "Net-(UA3-2A)") (class "Default")
      (node (ref "RA17") (pin "1") (pinfunction "1_1") (pintype "passive"))
      (node (ref "UA3") (pin "9") (pinfunction "2A_9") (pintype "passive"))
    )
    (net (code "84") (name "Net-(UA3-2B1)") (class "Default")
      (node (ref "RA14") (pin "1") (pinfunction "1_1") (pintype "passive"))
      (node (ref "UA3") (pin "10") (pinfunction "2B1_10") (pintype "passive"))
    )
    (net (code "85") (name "Net-(UA3-2B2)") (class "Default")
      (node (ref "RA16") (pin "1") (pinfunction "1_1") (pintype "passive"))
      (node (ref "UA3") (pin "11") (pinfunction "2B2_11") (pintype "passive"))
    )
    (net (code "86") (name "Net-(UA3-2B3)") (class "Default")
      (node (ref "RA15") (pin "1") (pinfunction "1_1") (pintype "passive"))
      (node (ref "UA3") (pin "12") (pinfunction "2B3_12") (pintype "passive"))
    )
    (net (code "87") (name "Net-(UA3-2B4)") (class "Default")
      (node (ref "RA12") (pin "2") (pinfunction "2_2") (pintype "passive"))
      (node (ref "RA14") (pin "2") (pinfunction "2_2") (pintype "passive"))
      (node (ref "RA15") (pin "2") (pinfunction "2_2") (pintype "passive"))
      (node (ref "RA16") (pin "2") (pinfunction "2_2") (pintype "passive"))
      (node (ref "UA3") (pin "13") (pinfunction "2B4_13") (pintype "passive"))
    )
    (net (code "88") (name "Net-(UA4-IN+)") (class "Default")
      (node (ref "RA28") (pin "2") (pinfunction "2_2") (pintype "passive"))
      (node (ref "RA29") (pin "1") (pinfunction "1_1") (pintype "passive"))
      (node (ref "UA4") (pin "8") (pinfunction "IN+_8") (pintype "passive"))
    )
    (net (code "89") (name "Net-(UA4-IN-)") (class "Default")
      (node (ref "RA13") (pin "1") (pinfunction "1_1") (pintype "passive"))
      (node (ref "RA18") (pin "2") (pinfunction "2_2") (pintype "passive"))
      (node (ref "UA4") (pin "1") (pinfunction "IN-_1") (pintype "passive"))
    )
    (net (code "90") (name "Net-(UA4-OUT+)") (class "Default")
      (node (ref "RA17") (pin "2") (pinfunction "2_2") (pintype "passive"))
      (node (ref "RA18") (pin "1") (pinfunction "1_1") (pintype "passive"))
      (node (ref "UA4") (pin "4") (pinfunction "OUT+_4") (pintype "passive"))
    )
    (net (code "91") (name "Net-(UA4-OUT-)") (class "Default")
      (node (ref "RA27") (pin "2") (pinfunction "2_2") (pintype "passive"))
      (node (ref "RA28") (pin "1") (pinfunction "1_1") (pintype "passive"))
      (node (ref "UA4") (pin "5") (pinfunction "OUT-_5") (pintype "passive"))
    )
    (net (code "92") (name "Net-(UA5-IN+)") (class "Default")
      (node (ref "RA46") (pin "2") (pinfunction "2_2") (pintype "passive"))
      (node (ref "RA47") (pin "1") (pinfunction "1_1") (pintype "passive"))
      (node (ref "UA5") (pin "8") (pinfunction "IN+_8") (pintype "passive"))
    )
    (net (code "93") (name "Net-(UA5-IN-)") (class "Default")
      (node (ref "RA32") (pin "2") (pinfunction "2_2") (pintype "passive"))
      (node (ref "RA33") (pin "1") (pinfunction "1_1") (pintype "passive"))
      (node (ref "UA5") (pin "1") (pinfunction "IN-_1") (pintype "passive"))
    )
    (net (code "94") (name "Net-(UA5-OUT+)") (class "Default")
      (node (ref "RA32") (pin "1") (pinfunction "1_1") (pintype "passive"))
      (node (ref "RA40") (pin "2") (pinfunction "2_2") (pintype "passive"))
      (node (ref "UA5") (pin "4") (pinfunction "OUT+_4") (pintype "passive"))
    )
    (net (code "95") (name "Net-(UA5-OUT-)") (class "Default")
      (node (ref "RA42") (pin "2") (pinfunction "2_2") (pintype "passive"))
      (node (ref "RA46") (pin "1") (pinfunction "1_1") (pintype "passive"))
      (node (ref "UA5") (pin "5") (pinfunction "OUT-_5") (pintype "passive"))
    )
    (net (code "96") (name "Net-(UA6-1A)") (class "Default")
      (node (ref "RA51") (pin "1") (pinfunction "1_1") (pintype "passive"))
      (node (ref "UA6") (pin "7") (pinfunction "1A_7") (pintype "passive"))
    )
    (net (code "97") (name "Net-(UA6-1B1)") (class "Default")
      (node (ref "RA48") (pin "2") (pinfunction "2_2") (pintype "passive"))
      (node (ref "UA6") (pin "6") (pinfunction "1B1_6") (pintype "passive"))
    )
    (net (code "98") (name "Net-(UA6-1B2)") (class "Default")
      (node (ref "RA45") (pin "2") (pinfunction "2_2") (pintype "passive"))
      (node (ref "UA6") (pin "5") (pinfunction "1B2_5") (pintype "passive"))
    )
    (net (code "99") (name "Net-(UA6-1B3)") (class "Default")
      (node (ref "RA50") (pin "2") (pinfunction "2_2") (pintype "passive"))
      (node (ref "UA6") (pin "4") (pinfunction "1B3_4") (pintype "passive"))
    )
    (net (code "100") (name "Net-(UA6-1B4)") (class "Default")
      (node (ref "RA45") (pin "1") (pinfunction "1_1") (pintype "passive"))
      (node (ref "RA47") (pin "2") (pinfunction "2_2") (pintype "passive"))
      (node (ref "RA48") (pin "1") (pinfunction "1_1") (pintype "passive"))
      (node (ref "RA50") (pin "1") (pinfunction "1_1") (pintype "passive"))
      (node (ref "UA6") (pin "3") (pinfunction "1B4_3") (pintype "passive"))
    )
    (net (code "101") (name "Net-(UA6-2A)") (class "Default")
      (node (ref "RA34") (pin "1") (pinfunction "1_1") (pintype "passive"))
      (node (ref "UA6") (pin "9") (pinfunction "2A_9") (pintype "passive"))
    )
    (net (code "102") (name "Net-(UA6-2B1)") (class "Default")
      (node (ref "RA39") (pin "1") (pinfunction "1_1") (pintype "passive"))
      (node (ref "UA6") (pin "10") (pinfunction "2B1_10") (pintype "passive"))
    )
    (net (code "103") (name "Net-(UA6-2B2)") (class "Default")
      (node (ref "RA38") (pin "1") (pinfunction "1_1") (pintype "passive"))
      (node (ref "UA6") (pin "11") (pinfunction "2B2_11") (pintype "passive"))
    )
    (net (code "104") (name "Net-(UA6-2B3)") (class "Default")
      (node (ref "RA37") (pin "1") (pinfunction "1_1") (pintype "passive"))
      (node (ref "UA6") (pin "12") (pinfunction "2B3_12") (pintype "passive"))
    )
    (net (code "105") (name "Net-(UA6-2B4)") (class "Default")
      (node (ref "RA33") (pin "2") (pinfunction "2_2") (pintype "passive"))
      (node (ref "RA37") (pin "2") (pinfunction "2_2") (pintype "passive"))
      (node (ref "RA38") (pin "2") (pinfunction "2_2") (pintype "passive"))
      (node (ref "RA39") (pin "2") (pinfunction "2_2") (pintype "passive"))
      (node (ref "UA6") (pin "13") (pinfunction "2B4_13") (pintype "passive"))
    )
    (net (code "106") (name "Net-(UA7-IN+)") (class "Default")
      (node (ref "RA52") (pin "2") (pinfunction "2_2") (pintype "passive"))
      (node (ref "RA53") (pin "1") (pinfunction "1_1") (pintype "passive"))
      (node (ref "UA7") (pin "8") (pinfunction "IN+_8") (pintype "passive"))
    )
    (net (code "107") (name "Net-(UA7-IN-)") (class "Default")
      (node (ref "RA35") (pin "2") (pinfunction "2_2") (pintype "passive"))
      (node (ref "RA36") (pin "1") (pinfunction "1_1") (pintype "passive"))
      (node (ref "UA7") (pin "1") (pinfunction "IN-_1") (pintype "passive"))
    )
    (net (code "108") (name "Net-(UA7-OUT+)") (class "Default")
      (node (ref "RA34") (pin "2") (pinfunction "2_2") (pintype "passive"))
      (node (ref "RA35") (pin "1") (pinfunction "1_1") (pintype "passive"))
      (node (ref "UA7") (pin "4") (pinfunction "OUT+_4") (pintype "passive"))
    )
    (net (code "109") (name "Net-(UA7-OUT-)") (class "Default")
      (node (ref "RA51") (pin "2") (pinfunction "2_2") (pintype "passive"))
      (node (ref "RA52") (pin "1") (pinfunction "1_1") (pintype "passive"))
      (node (ref "UA7") (pin "5") (pinfunction "OUT-_5") (pintype "passive"))
    )
    (net (code "110") (name "VCC3Vp") (class "Default")
      (node (ref "CA15") (pin "1") (pinfunction "1_1") (pintype "passive"))
      (node (ref "CA18") (pin "1") (pinfunction "1_1") (pintype "passive"))
      (node (ref "CA27") (pin "1") (pinfunction "1_1") (pintype "passive"))
      (node (ref "CA4") (pin "1") (pinfunction "1_1") (pintype "passive"))
      (node (ref "RA44") (pin "2") (pinfunction "2_2") (pintype "passive"))
      (node (ref "RA9") (pin "2") (pinfunction "2_2") (pintype "passive"))
      (node (ref "UA1") (pin "10") (pinfunction "VDD_10") (pintype "passive"))
      (node (ref "UA1") (pin "18") (pinfunction "VDD_18") (pintype "passive"))
      (node (ref "UA1") (pin "63") (pinfunction "VDD_63") (pintype "passive"))
      (node (ref "UA1") (pin "7") (pinfunction "VDD_7") (pintype "passive"))
    )
    (net (code "111") (name "VCC5Vn") (class "Default")
      (node (ref "CA16") (pin "1") (pinfunction "1_1") (pintype "passive"))
      (node (ref "CA17") (pin "2") (pinfunction "2_2") (pintype "passive"))
      (node (ref "CA32") (pin "1") (pinfunction "1_1") (pintype "passive"))
      (node (ref "CA34") (pin "2") (pinfunction "2_2") (pintype "passive"))
      (node (ref "CA38") (pin "1") (pinfunction "1_1") (pintype "passive"))
      (node (ref "CA39") (pin "2") (pinfunction "2_2") (pintype "passive"))
      (node (ref "CA42") (pin "1") (pinfunction "1_1") (pintype "passive"))
      (node (ref "CA43") (pin "2") (pinfunction "2_2") (pintype "passive"))
      (node (ref "UA2") (pin "6") (pinfunction "VCC-_6") (pintype "passive"))
      (node (ref "UA4") (pin "6") (pinfunction "VCC-_6") (pintype "passive"))
      (node (ref "UA5") (pin "6") (pinfunction "VCC-_6") (pintype "passive"))
      (node (ref "UA7") (pin "6") (pinfunction "VCC-_6") (pintype "passive"))
    )
    (net (code "112") (name "VCC5Vp") (class "Default")
      (node (ref "CA23") (pin "1") (pinfunction "1_1") (pintype "passive"))
      (node (ref "CA24") (pin "1") (pinfunction "1_1") (pintype "passive"))
      (node (ref "CA3") (pin "1") (pinfunction "1_1") (pintype "passive"))
      (node (ref "CA36") (pin "1") (pinfunction "1_1") (pintype "passive"))
      (node (ref "CA37") (pin "1") (pinfunction "1_1") (pintype "passive"))
      (node (ref "CA40") (pin "1") (pinfunction "1_1") (pintype "passive"))
      (node (ref "CA41") (pin "1") (pinfunction "1_1") (pintype "passive"))
      (node (ref "CA5") (pin "1") (pinfunction "1_1") (pintype "passive"))
      (node (ref "CD81") (pin "1") (pinfunction "1_1") (pintype "passive"))
      (node (ref "CD82") (pin "1") (pinfunction "1_1") (pintype "passive"))
      (node (ref "RA10") (pin "1") (pinfunction "1_1") (pintype "passive"))
      (node (ref "RA30") (pin "1") (pinfunction "1_1") (pintype "passive"))
      (node (ref "RA31") (pin "1") (pinfunction "1_1") (pintype "passive"))
      (node (ref "RA55") (pin "1") (pinfunction "1_1") (pintype "passive"))
      (node (ref "UA2") (pin "3") (pinfunction "VCC+_3") (pintype "passive"))
      (node (ref "UA3") (pin "16") (pinfunction "VCC5_16") (pintype "passive"))
      (node (ref "UA4") (pin "3") (pinfunction "VCC+_3") (pintype "passive"))
      (node (ref "UA5") (pin "3") (pinfunction "VCC+_3") (pintype "passive"))
      (node (ref "UA6") (pin "16") (pinfunction "VCC5_16") (pintype "passive"))
      (node (ref "UA7") (pin "3") (pinfunction "VCC+_3") (pintype "passive"))
    )
    (net (code "113") (name "VDD3V") (class "Default")
      (node (ref "CA25") (pin "1") (pinfunction "1_1") (pintype "passive"))
      (node (ref "CA44") (pin "1") (pinfunction "1_1") (pintype "passive"))
      (node (ref "CA45") (pin "1") (pinfunction "1_1") (pintype "passive"))
      (node (ref "CA7") (pin "2") (pinfunction "2_2") (pintype "passive"))
      (node (ref "RA2") (pin "1") (pinfunction "1_1") (pintype "passive"))
      (node (ref "RA4") (pin "1") (pinfunction "1_1") (pintype "passive"))
      (node (ref "RA56") (pin "1") (pinfunction "1_1") (pintype "passive"))
      (node (ref "RA6") (pin "1") (pinfunction "1_1") (pintype "passive"))
      (node (ref "UA1") (pin "32") (pinfunction "0VDD_32") (pintype "passive"))
      (node (ref "UA1") (pin "49") (pinfunction "OVDD_49") (pintype "passive"))
    )
    (net (code "114") (name "unconnected-(UA2-NC-Pad7)") (class "Default")
      (node (ref "UA2") (pin "7") (pinfunction "NC_7") (pintype "passive"))
    )
    (net (code "115") (name "unconnected-(UA4-NC-Pad7)") (class "Default")
      (node (ref "UA4") (pin "7") (pinfunction "NC_7") (pintype "passive"))
    )
    (net (code "116") (name "unconnected-(UA5-NC-Pad7)") (class "Default")
      (node (ref "UA5") (pin "7") (pinfunction "NC_7") (pintype "passive"))
    )
    (net (code "117") (name "unconnected-(UA7-NC-Pad7)") (class "Default")
      (node (ref "UA7") (pin "7") (pinfunction "NC_7") (pintype "passive"))
    )
  )
)
